# 1-Schematic__980.net
KiCad netlist of a schematic drawn in EasyEDA
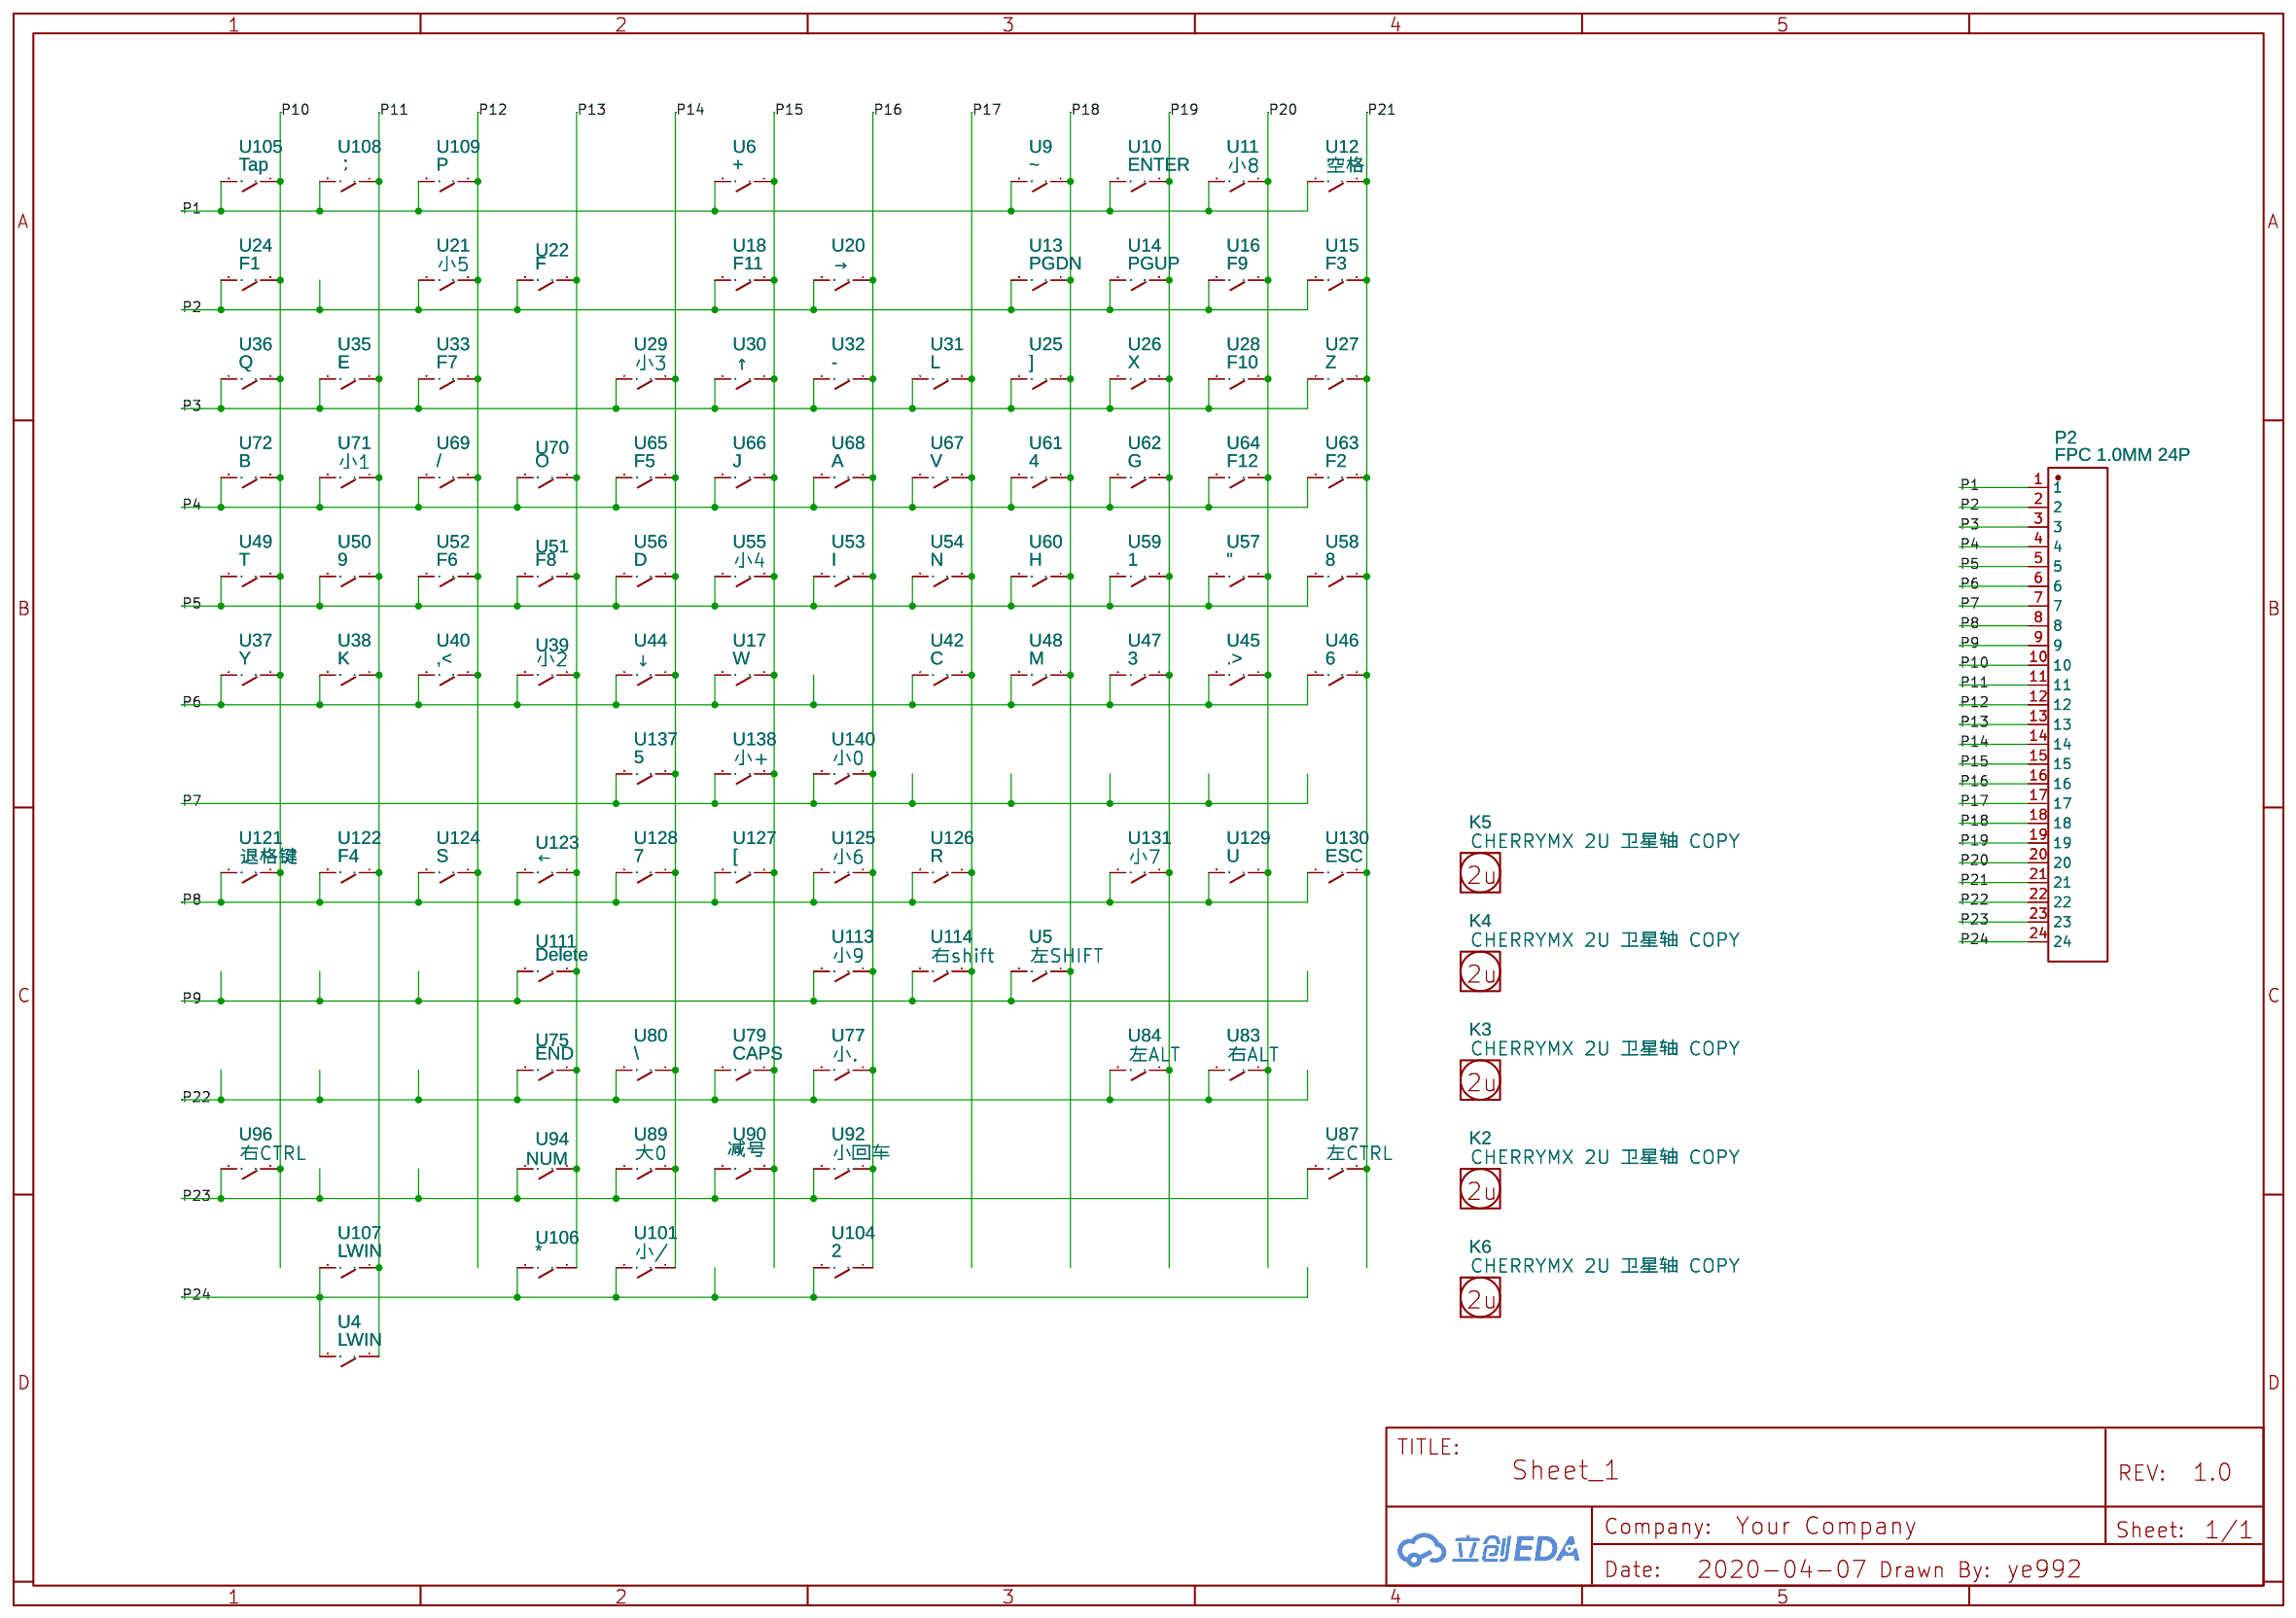
[diagram p0: 布局]
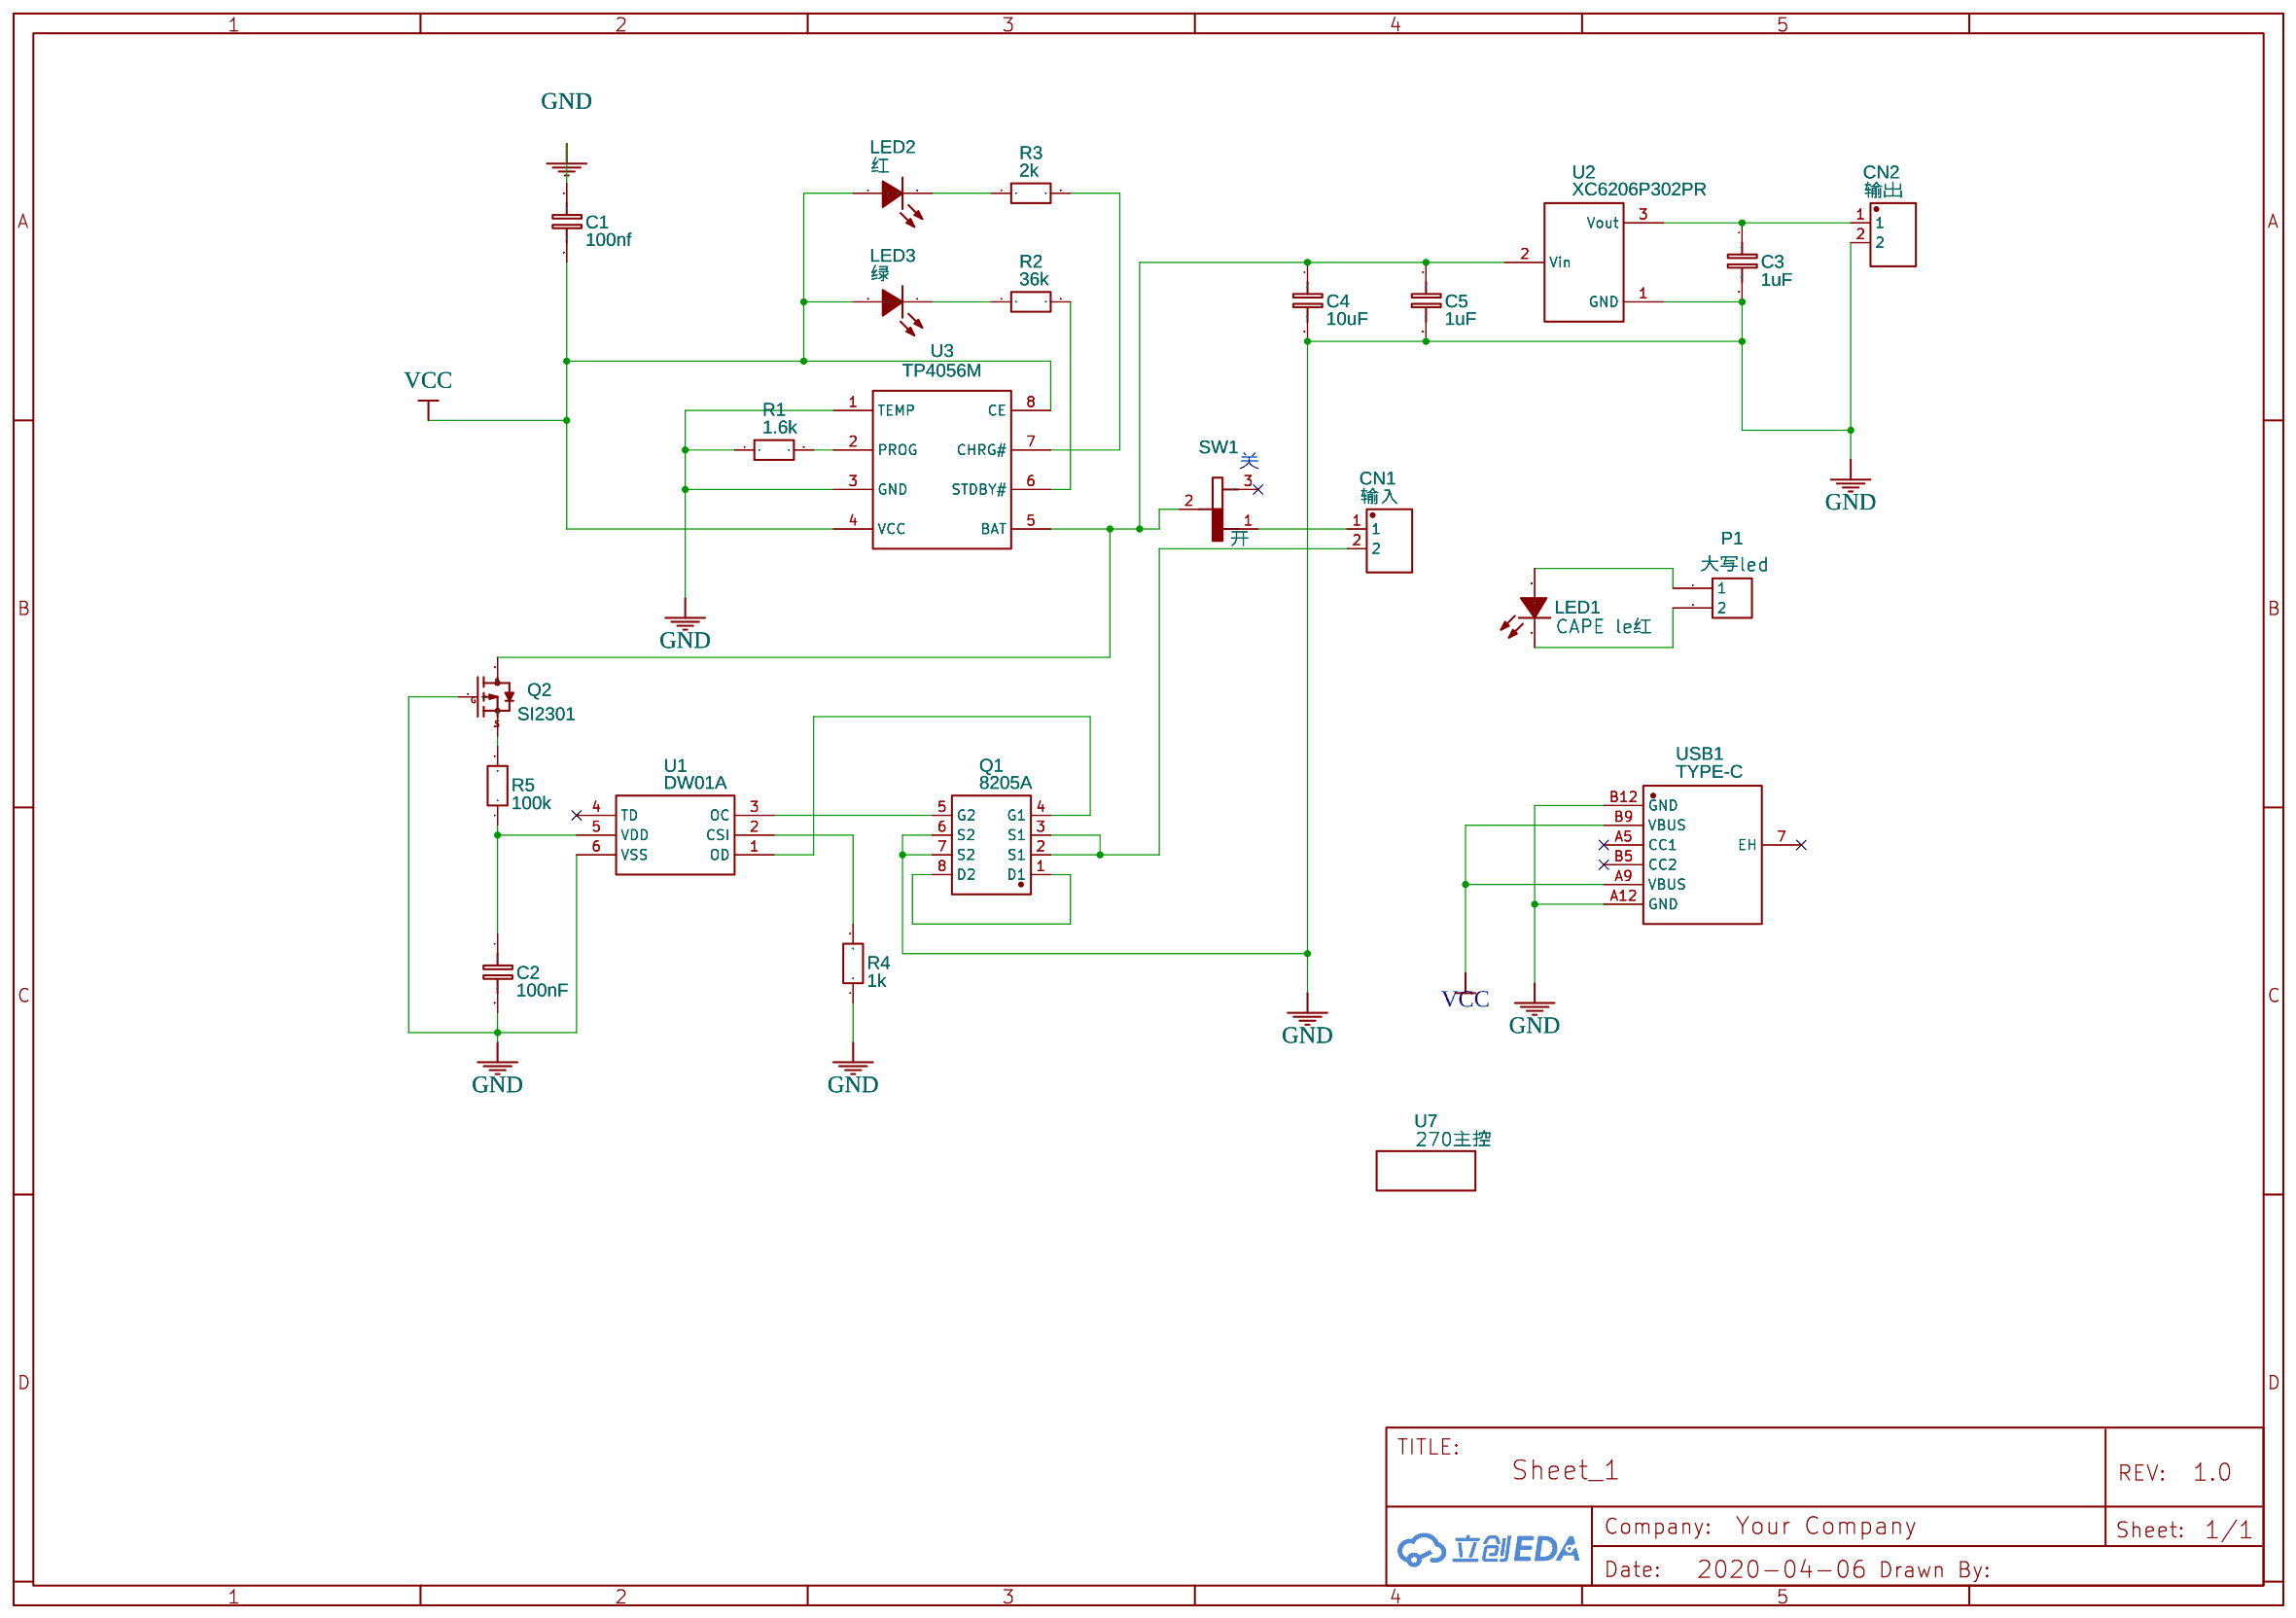
[diagram p1: Sheet_1]

(export (version "E")
  (design (tool "Eeschema 10.0.6"))
  (components
    (comp (ref "K2")
      (value "CHERRYMX 2U 卫星轴 COPY")
      (fields (field (name "BOM_Manufacturer Part") "Cherry MX"))
      (libsource (lib "") (part "CHERRYMX 2U 卫星轴 COPY"))
    )
    (comp (ref "K3")
      (value "CHERRYMX 2U 卫星轴 COPY")
      (fields (field (name "BOM_Manufacturer Part") "Cherry MX"))
      (libsource (lib "") (part "CHERRYMX 2U 卫星轴 COPY"))
    )
    (comp (ref "K4")
      (value "CHERRYMX 2U 卫星轴 COPY")
      (fields (field (name "BOM_Manufacturer Part") "Cherry MX"))
      (libsource (lib "") (part "CHERRYMX 2U 卫星轴 COPY"))
    )
    (comp (ref "K5")
      (value "CHERRYMX 2U 卫星轴 COPY")
      (fields (field (name "BOM_Manufacturer Part") "Cherry MX"))
      (libsource (lib "") (part "CHERRYMX 2U 卫星轴 COPY"))
    )
    (comp (ref "K6")
      (value "CHERRYMX 2U 卫星轴 COPY")
      (fields (field (name "BOM_Manufacturer Part") "Cherry MX"))
      (libsource (lib "") (part "CHERRYMX 2U 卫星轴 COPY"))
    )
    (comp (ref "P2")
      (value "FPC 1.0MM 24P")
      (fields
        (field (name "BOM_Manufacturer Part") "FPC 1.0mmpitch 24P Pull type Under the next")
        (field (name "BOM_Supplier Part") "C48186")
      )
      (libsource (lib "") (part "fpc24p （FPC 1.0MM 24P NO CONNECTOR）"))
    )
    (comp (ref "U4") (value "LWIN") (libsource (lib "") (part "CHERRY")))
    (comp (ref "U5") (value "左SHIFT") (libsource (lib "") (part "CHERRY")))
    (comp (ref "U6") (value "+") (libsource (lib "") (part "CHERRY")))
    (comp (ref "U9") (value "~") (libsource (lib "") (part "CHERRY")))
    (comp (ref "U10") (value "ENTER") (libsource (lib "") (part "CHERRY")))
    (comp (ref "U11") (value "小8") (libsource (lib "") (part "CHERRY")))
    (comp (ref "U12") (value "空格") (libsource (lib "") (part "CHERRY")))
    (comp (ref "U13") (value "PGDN") (libsource (lib "") (part "CHERRY")))
    (comp (ref "U14") (value "PGUP") (libsource (lib "") (part "CHERRY")))
    (comp (ref "U15") (value "F3") (libsource (lib "") (part "CHERRY")))
    (comp (ref "U16") (value "F9") (libsource (lib "") (part "CHERRY")))
    (comp (ref "U17") (value "W") (libsource (lib "") (part "CHERRY")))
    (comp (ref "U18") (value "F11") (libsource (lib "") (part "CHERRY")))
    (comp (ref "U20") (value "→") (libsource (lib "") (part "CHERRY")))
    (comp (ref "U21") (value "小5") (libsource (lib "") (part "CHERRY")))
    (comp (ref "U22") (value "F") (libsource (lib "") (part "CHERRY")))
    (comp (ref "U24") (value "F1") (libsource (lib "") (part "CHERRY")))
    (comp (ref "U25") (value "]") (libsource (lib "") (part "CHERRY")))
    (comp (ref "U26") (value "X") (libsource (lib "") (part "CHERRY")))
    (comp (ref "U27") (value "Z") (libsource (lib "") (part "CHERRY")))
    (comp (ref "U28") (value "F10") (libsource (lib "") (part "CHERRY")))
    (comp (ref "U29") (value "小3") (libsource (lib "") (part "CHERRY")))
    (comp (ref "U30") (value "↑") (libsource (lib "") (part "CHERRY")))
    (comp (ref "U31") (value "L") (libsource (lib "") (part "CHERRY")))
    (comp (ref "U32") (value "-") (libsource (lib "") (part "CHERRY")))
    (comp (ref "U33") (value "F7") (libsource (lib "") (part "CHERRY")))
    (comp (ref "U35") (value "E") (libsource (lib "") (part "CHERRY")))
    (comp (ref "U36") (value "Q") (libsource (lib "") (part "CHERRY")))
    (comp (ref "U37") (value "Y") (libsource (lib "") (part "CHERRY")))
    (comp (ref "U38") (value "K") (libsource (lib "") (part "CHERRY")))
    (comp (ref "U39") (value "小2") (libsource (lib "") (part "CHERRY")))
    (comp (ref "U40") (value ",<") (libsource (lib "") (part "CHERRY")))
    (comp (ref "U42") (value "C") (libsource (lib "") (part "CHERRY")))
    (comp (ref "U44") (value "↓") (libsource (lib "") (part "CHERRY")))
    (comp (ref "U45") (value ".>") (libsource (lib "") (part "CHERRY")))
    (comp (ref "U46") (value "6") (libsource (lib "") (part "CHERRY")))
    (comp (ref "U47") (value "3") (libsource (lib "") (part "CHERRY")))
    (comp (ref "U48") (value "M") (libsource (lib "") (part "CHERRY")))
    (comp (ref "U49") (value "T") (libsource (lib "") (part "CHERRY")))
    (comp (ref "U50") (value "9") (libsource (lib "") (part "CHERRY")))
    (comp (ref "U51") (value "F8") (libsource (lib "") (part "CHERRY")))
    (comp (ref "U52") (value "F6") (libsource (lib "") (part "CHERRY")))
    (comp (ref "U53") (value "I") (libsource (lib "") (part "CHERRY")))
    (comp (ref "U54") (value "N") (libsource (lib "") (part "CHERRY")))
    (comp (ref "U55") (value "小4") (libsource (lib "") (part "CHERRY")))
    (comp (ref "U56") (value "D") (libsource (lib "") (part "CHERRY")))
    (comp (ref "U57") (value "\"") (libsource (lib "") (part "CHERRY")))
    (comp (ref "U58") (value "8") (libsource (lib "") (part "CHERRY")))
    (comp (ref "U59") (value "1") (libsource (lib "") (part "CHERRY")))
    (comp (ref "U60") (value "H") (libsource (lib "") (part "CHERRY")))
    (comp (ref "U61") (value "4") (libsource (lib "") (part "CHERRY")))
    (comp (ref "U62") (value "G") (libsource (lib "") (part "CHERRY")))
    (comp (ref "U63") (value "F2") (libsource (lib "") (part "CHERRY")))
    (comp (ref "U64") (value "F12") (libsource (lib "") (part "CHERRY")))
    (comp (ref "U65") (value "F5") (libsource (lib "") (part "CHERRY")))
    (comp (ref "U66") (value "J") (libsource (lib "") (part "CHERRY")))
    (comp (ref "U67") (value "V") (libsource (lib "") (part "CHERRY")))
    (comp (ref "U68") (value "A") (libsource (lib "") (part "CHERRY")))
    (comp (ref "U69") (value "/") (libsource (lib "") (part "CHERRY")))
    (comp (ref "U70") (value "O") (libsource (lib "") (part "CHERRY")))
    (comp (ref "U71") (value "小1") (libsource (lib "") (part "CHERRY")))
    (comp (ref "U72") (value "B") (libsource (lib "") (part "CHERRY")))
    (comp (ref "U75") (value "END") (libsource (lib "") (part "CHERRY")))
    (comp (ref "U77") (value "小.") (libsource (lib "") (part "CHERRY")))
    (comp (ref "U79") (value "CAPS") (libsource (lib "") (part "CHERRY")))
    (comp (ref "U80") (value "\\") (libsource (lib "") (part "CHERRY")))
    (comp (ref "U83") (value "右ALT") (libsource (lib "") (part "CHERRY")))
    (comp (ref "U84") (value "左ALT") (libsource (lib "") (part "CHERRY")))
    (comp (ref "U87") (value "左CTRL") (libsource (lib "") (part "CHERRY")))
    (comp (ref "U89") (value "大0") (libsource (lib "") (part "CHERRY")))
    (comp (ref "U90") (value "减号") (libsource (lib "") (part "CHERRY")))
    (comp (ref "U92") (value "小回车") (libsource (lib "") (part "CHERRY")))
    (comp (ref "U94") (value "NUM") (libsource (lib "") (part "CHERRY")))
    (comp (ref "U96") (value "右CTRL") (libsource (lib "") (part "CHERRY")))
    (comp (ref "U101") (value "小/") (libsource (lib "") (part "CHERRY")))
    (comp (ref "U104") (value "2") (libsource (lib "") (part "CHERRY")))
    (comp (ref "U105") (value "Tap") (libsource (lib "") (part "CHERRY")))
    (comp (ref "U106") (value "*") (libsource (lib "") (part "CHERRY")))
    (comp (ref "U107") (value "LWIN") (libsource (lib "") (part "CHERRY")))
    (comp (ref "U108") (value "；") (libsource (lib "") (part "CHERRY")))
    (comp (ref "U109") (value "P") (libsource (lib "") (part "CHERRY")))
    (comp (ref "U111") (value "Delete") (libsource (lib "") (part "CHERRY")))
    (comp (ref "U113") (value "小9") (libsource (lib "") (part "CHERRY")))
    (comp (ref "U114") (value "右shift") (libsource (lib "") (part "CHERRY")))
    (comp (ref "U121") (value "退格键") (libsource (lib "") (part "CHERRY")))
    (comp (ref "U122") (value "F4") (libsource (lib "") (part "CHERRY")))
    (comp (ref "U123") (value "←") (libsource (lib "") (part "CHERRY")))
    (comp (ref "U124") (value "S") (libsource (lib "") (part "CHERRY")))
    (comp (ref "U125") (value "小6") (libsource (lib "") (part "CHERRY")))
    (comp (ref "U126") (value "R") (libsource (lib "") (part "CHERRY")))
    (comp (ref "U127") (value "[") (libsource (lib "") (part "CHERRY")))
    (comp (ref "U128") (value "7") (libsource (lib "") (part "CHERRY")))
    (comp (ref "U129") (value "U") (libsource (lib "") (part "CHERRY")))
    (comp (ref "U130") (value "ESC") (libsource (lib "") (part "CHERRY")))
    (comp (ref "U131") (value "小7") (libsource (lib "") (part "CHERRY")))
    (comp (ref "U137") (value "5") (libsource (lib "") (part "CHERRY")))
    (comp (ref "U138") (value "小+") (libsource (lib "") (part "CHERRY")))
    (comp (ref "U140") (value "小0") (libsource (lib "") (part "CHERRY")))
    (comp (ref "C1") (value "100nf") (libsource (lib "") (part "Cap_1206_EU")))
    (comp (ref "C2") (value "100nF") (libsource (lib "") (part "Cap_1206_EU_2")))
    (comp (ref "C3") (value "1uF") (libsource (lib "") (part "Cap_1206_EU_1")))
    (comp (ref "C4") (value "10uF") (libsource (lib "") (part "Cap_1206_EU_1")))
    (comp (ref "C5") (value "1uF") (libsource (lib "") (part "Cap_1206_EU_1")))
    (comp (ref "CN1")
      (value "输入")
      (fields (field (name "BOM_Manufacturer Part") "2510S-2P") (field (name "BOM_Supplier Part") "C132504"))
      (libsource (lib "") (part "2510S-2P"))
    )
    (comp (ref "CN2")
      (value "输出")
      (fields (field (name "BOM_Manufacturer Part") "2510S-2P") (field (name "BOM_Supplier Part") "C132504"))
      (libsource (lib "") (part "2510S-2P"))
    )
    (comp (ref "LED1")
      (value "CAPE le红")
      (fields
        (field (name "BOM_Manufacturer Part") "FC-3215HRK-620D")
        (field (name "BOM_Supplier Part") "C84270")
      )
      (libsource (lib "") (part "FC-3215HRK-620D"))
    )
    (comp (ref "LED2")
      (value "红")
      (fields
        (field (name "BOM_Manufacturer Part") "FC-3215HRK-620D")
        (field (name "BOM_Supplier Part") "C84270")
      )
      (libsource (lib "") (part "FC-3215HRK-620D_1"))
    )
    (comp (ref "LED3")
      (value "绿")
      (fields
        (field (name "BOM_Manufacturer Part") "FC-3215UGK-520D")
        (field (name "BOM_Supplier Part") "C99881")
      )
      (libsource (lib "") (part "FC-3215UGK-520D"))
    )
    (comp (ref "P1")
      (value "大写led")
      (fields
        (field (name "BOM_Manufacturer Part") "2.54mm 1*2P")
        (field (name "BOM_Supplier Part") "C36717")
      )
      (libsource (lib "") (part "2.54mm 1*2P"))
    )
    (comp (ref "Q1")
      (value "8205A")
      (fields (field (name "BOM_Supplier Part") "C181100"))
      (libsource (lib "") (part "8205A"))
    )
    (comp (ref "Q2")
      (value "SI2301")
      (fields (field (name "BOM_Supplier Part") "C181086"))
      (libsource (lib "") (part "SI2301"))
    )
    (comp (ref "R1") (value "1.6k") (libsource (lib "") (part "Res_1206(1/4W)_EU_1")))
    (comp (ref "R2") (value "36k") (libsource (lib "") (part "Res_1206(1/4W)_EU_1")))
    (comp (ref "R3") (value "2k") (libsource (lib "") (part "Res_1206(1/4W)_EU_1")))
    (comp (ref "R4") (value "1k") (libsource (lib "") (part "Res_1206(1/4W)_EU")))
    (comp (ref "R5") (value "100k") (libsource (lib "") (part "Res_1206(1/4W)_EU")))
    (comp (ref "SW1")
      (value "开")
      (fields
        (field (name "BOM_Manufacturer Part") "CSJ-1206-PAP31-14R")
        (field (name "BOM_Supplier Part") "C248278")
      )
      (libsource (lib "") (part "CSJ-1206-PAP31-14R"))
    )
    (comp (ref "U1")
      (value "DW01A")
      (fields (field (name "BOM_Supplier Part") "C85680"))
      (libsource (lib "") (part "DW01A"))
    )
    (comp (ref "U2")
      (value "XC6206P302PR")
      (fields (field (name "BOM_Supplier Part") "C34506"))
      (libsource (lib "") (part "XC6206P302PR"))
    )
    (comp (ref "U3")
      (value "TP4056M")
      (fields (field (name "BOM_Supplier Part") "C21417"))
      (libsource (lib "") (part "TP4056M"))
    )
    (comp (ref "U7") (value "270主控") (libsource (lib "") (part "270主控")))
    (comp (ref "USB1")
      (value "TYPE-C")
      (fields (field (name "BOM_Manufacturer Part") "TYPE-C 6P") (field (name "BOM_Supplier Part") "C456012"))
      (libsource (lib "") (part "TYPE-C 6P"))
    )
  )
  (nets
    (net (code "1") (name "GND") (class "Default")
      (node (ref "C1") (pin "1") (pinfunction "1_1") (pintype "unspecified"))
      (node (ref "C2") (pin "2") (pinfunction "2_2") (pintype "unspecified"))
      (node (ref "C3") (pin "2") (pinfunction "2_2") (pintype "unspecified"))
      (node (ref "C4") (pin "2") (pinfunction "2_2") (pintype "unspecified"))
      (node (ref "C5") (pin "2") (pinfunction "2_2") (pintype "unspecified"))
      (node (ref "CN2") (pin "2") (pinfunction "2_2") (pintype "unspecified"))
      (node (ref "Q1") (pin "6") (pinfunction "S2_6") (pintype "unspecified"))
      (node (ref "Q1") (pin "7") (pinfunction "S2_7") (pintype "unspecified"))
      (node (ref "Q2") (pin "1") (pinfunction "G_1") (pintype "unspecified"))
      (node (ref "R1") (pin "1") (pinfunction "1_1") (pintype "unspecified"))
      (node (ref "R4") (pin "1") (pinfunction "1_1") (pintype "unspecified"))
      (node (ref "U1") (pin "6") (pinfunction "VSS_6") (pintype "unspecified"))
      (node (ref "U2") (pin "1") (pinfunction "GND_1") (pintype "unspecified"))
      (node (ref "U3") (pin "1") (pinfunction "TEMP_1") (pintype "unspecified"))
      (node (ref "U3") (pin "3") (pinfunction "GND_3") (pintype "unspecified"))
      (node (ref "USB1") (pin "A12") (pinfunction "GND_A12") (pintype "unspecified"))
      (node (ref "USB1") (pin "B12") (pinfunction "GND_B12") (pintype "unspecified"))
    )
    (net (code "2") (name "Net-(CN1-Pad1)") (class "Default")
      (node (ref "CN1") (pin "1") (pinfunction "1_1") (pintype "unspecified"))
      (node (ref "SW1") (pin "1") (pinfunction "1_1") (pintype "unspecified"))
    )
    (net (code "3") (name "Net-(CN1-Pad2)") (class "Default")
      (node (ref "CN1") (pin "2") (pinfunction "2_2") (pintype "unspecified"))
      (node (ref "Q1") (pin "2") (pinfunction "S1_2") (pintype "unspecified"))
      (node (ref "Q1") (pin "3") (pinfunction "S1_3") (pintype "unspecified"))
    )
    (net (code "4") (name "Net-(LED1-A)") (class "Default")
      (node (ref "LED1") (pin "1") (pinfunction "A_1") (pintype "unspecified"))
      (node (ref "P1") (pin "1") (pinfunction "1_1") (pintype "input"))
    )
    (net (code "5") (name "Net-(LED1-K)") (class "Default")
      (node (ref "LED1") (pin "2") (pinfunction "K_2") (pintype "unspecified"))
      (node (ref "P1") (pin "2") (pinfunction "2_2") (pintype "input"))
    )
    (net (code "6") (name "Net-(LED2-K)") (class "Default")
      (node (ref "LED2") (pin "2") (pinfunction "K_2") (pintype "unspecified"))
      (node (ref "R3") (pin "1") (pinfunction "1_1") (pintype "unspecified"))
    )
    (net (code "7") (name "Net-(LED3--)") (class "Default")
      (node (ref "LED3") (pin "1") (pinfunction "-_1") (pintype "unspecified"))
      (node (ref "R2") (pin "1") (pinfunction "1_1") (pintype "unspecified"))
    )
    (net (code "8") (name "Net-(Q1-D1)") (class "Default")
      (node (ref "Q1") (pin "1") (pinfunction "D1_1") (pintype "unspecified"))
      (node (ref "Q1") (pin "8") (pinfunction "D2_8") (pintype "unspecified"))
    )
    (net (code "9") (name "Net-(Q1-G1)") (class "Default")
      (node (ref "Q1") (pin "4") (pinfunction "G1_4") (pintype "unspecified"))
      (node (ref "U1") (pin "1") (pinfunction "OD_1") (pintype "unspecified"))
    )
    (net (code "10") (name "Net-(Q1-G2)") (class "Default")
      (node (ref "Q1") (pin "5") (pinfunction "G2_5") (pintype "unspecified"))
      (node (ref "U1") (pin "3") (pinfunction "OC_3") (pintype "unspecified"))
    )
    (net (code "11") (name "Net-(Q2-D)") (class "Default")
      (node (ref "C4") (pin "1") (pinfunction "1_1") (pintype "unspecified"))
      (node (ref "C5") (pin "1") (pinfunction "1_1") (pintype "unspecified"))
      (node (ref "Q2") (pin "3") (pinfunction "D_3") (pintype "unspecified"))
      (node (ref "SW1") (pin "2") (pinfunction "2_2") (pintype "unspecified"))
      (node (ref "U2") (pin "2") (pinfunction "Vin_2") (pintype "unspecified"))
      (node (ref "U3") (pin "5") (pinfunction "BAT_5") (pintype "unspecified"))
    )
    (net (code "12") (name "Net-(Q2-S)") (class "Default")
      (node (ref "Q2") (pin "2") (pinfunction "S_2") (pintype "unspecified"))
      (node (ref "R5") (pin "2") (pinfunction "2_2") (pintype "unspecified"))
    )
    (net (code "13") (name "Net-(U1-CSI)") (class "Default")
      (node (ref "R4") (pin "2") (pinfunction "2_2") (pintype "unspecified"))
      (node (ref "U1") (pin "2") (pinfunction "CSI_2") (pintype "unspecified"))
    )
    (net (code "14") (name "Net-(U1-VDD)") (class "Default")
      (node (ref "C2") (pin "1") (pinfunction "1_1") (pintype "unspecified"))
      (node (ref "R5") (pin "1") (pinfunction "1_1") (pintype "unspecified"))
      (node (ref "U1") (pin "5") (pinfunction "VDD_5") (pintype "unspecified"))
    )
    (net (code "15") (name "Net-(U2-Vout)") (class "Default")
      (node (ref "C3") (pin "1") (pinfunction "1_1") (pintype "unspecified"))
      (node (ref "CN2") (pin "1") (pinfunction "1_1") (pintype "unspecified"))
      (node (ref "U2") (pin "3") (pinfunction "Vout_3") (pintype "unspecified"))
    )
    (net (code "16") (name "Net-(U3-CHRG#)") (class "Default")
      (node (ref "R3") (pin "2") (pinfunction "2_2") (pintype "unspecified"))
      (node (ref "U3") (pin "7") (pinfunction "CHRG#_7") (pintype "unspecified"))
    )
    (net (code "17") (name "Net-(U3-PROG)") (class "Default")
      (node (ref "R1") (pin "2") (pinfunction "2_2") (pintype "unspecified"))
      (node (ref "U3") (pin "2") (pinfunction "PROG_2") (pintype "unspecified"))
    )
    (net (code "18") (name "Net-(U3-STDBY#)") (class "Default")
      (node (ref "R2") (pin "2") (pinfunction "2_2") (pintype "unspecified"))
      (node (ref "U3") (pin "6") (pinfunction "STDBY#_6") (pintype "unspecified"))
    )
    (net (code "19") (name "P1") (class "Default")
      (node (ref "P2") (pin "1") (pinfunction "1_1") (pintype "unspecified"))
      (node (ref "U10") (pin "2") (pinfunction "2_2") (pintype "input"))
      (node (ref "U105") (pin "2") (pinfunction "2_2") (pintype "input"))
      (node (ref "U108") (pin "2") (pinfunction "2_2") (pintype "input"))
      (node (ref "U109") (pin "2") (pinfunction "2_2") (pintype "input"))
      (node (ref "U11") (pin "2") (pinfunction "2_2") (pintype "input"))
      (node (ref "U12") (pin "2") (pinfunction "2_2") (pintype "input"))
      (node (ref "U6") (pin "2") (pinfunction "2_2") (pintype "input"))
      (node (ref "U9") (pin "2") (pinfunction "2_2") (pintype "input"))
    )
    (net (code "20") (name "P2") (class "Default")
      (node (ref "P2") (pin "2") (pinfunction "2_2") (pintype "unspecified"))
      (node (ref "U13") (pin "2") (pinfunction "2_2") (pintype "input"))
      (node (ref "U14") (pin "2") (pinfunction "2_2") (pintype "input"))
      (node (ref "U15") (pin "2") (pinfunction "2_2") (pintype "input"))
      (node (ref "U16") (pin "2") (pinfunction "2_2") (pintype "input"))
      (node (ref "U18") (pin "2") (pinfunction "2_2") (pintype "input"))
      (node (ref "U20") (pin "2") (pinfunction "2_2") (pintype "input"))
      (node (ref "U21") (pin "2") (pinfunction "2_2") (pintype "input"))
      (node (ref "U22") (pin "2") (pinfunction "2_2") (pintype "input"))
      (node (ref "U24") (pin "2") (pinfunction "2_2") (pintype "input"))
    )
    (net (code "21") (name "P3") (class "Default")
      (node (ref "P2") (pin "3") (pinfunction "3_3") (pintype "unspecified"))
      (node (ref "U25") (pin "2") (pinfunction "2_2") (pintype "input"))
      (node (ref "U26") (pin "2") (pinfunction "2_2") (pintype "input"))
      (node (ref "U27") (pin "2") (pinfunction "2_2") (pintype "input"))
      (node (ref "U28") (pin "2") (pinfunction "2_2") (pintype "input"))
      (node (ref "U29") (pin "2") (pinfunction "2_2") (pintype "input"))
      (node (ref "U30") (pin "2") (pinfunction "2_2") (pintype "input"))
      (node (ref "U31") (pin "2") (pinfunction "2_2") (pintype "input"))
      (node (ref "U32") (pin "2") (pinfunction "2_2") (pintype "input"))
      (node (ref "U33") (pin "2") (pinfunction "2_2") (pintype "input"))
      (node (ref "U35") (pin "2") (pinfunction "2_2") (pintype "input"))
      (node (ref "U36") (pin "2") (pinfunction "2_2") (pintype "input"))
    )
    (net (code "22") (name "P4") (class "Default")
      (node (ref "P2") (pin "4") (pinfunction "4_4") (pintype "unspecified"))
      (node (ref "U61") (pin "2") (pinfunction "2_2") (pintype "input"))
      (node (ref "U62") (pin "2") (pinfunction "2_2") (pintype "input"))
      (node (ref "U63") (pin "2") (pinfunction "2_2") (pintype "input"))
      (node (ref "U64") (pin "2") (pinfunction "2_2") (pintype "input"))
      (node (ref "U65") (pin "2") (pinfunction "2_2") (pintype "input"))
      (node (ref "U66") (pin "2") (pinfunction "2_2") (pintype "input"))
      (node (ref "U67") (pin "2") (pinfunction "2_2") (pintype "input"))
      (node (ref "U68") (pin "2") (pinfunction "2_2") (pintype "input"))
      (node (ref "U69") (pin "2") (pinfunction "2_2") (pintype "input"))
      (node (ref "U70") (pin "2") (pinfunction "2_2") (pintype "input"))
      (node (ref "U71") (pin "2") (pinfunction "2_2") (pintype "input"))
      (node (ref "U72") (pin "2") (pinfunction "2_2") (pintype "input"))
    )
    (net (code "23") (name "P5") (class "Default")
      (node (ref "P2") (pin "5") (pinfunction "5_5") (pintype "unspecified"))
      (node (ref "U49") (pin "2") (pinfunction "2_2") (pintype "input"))
      (node (ref "U50") (pin "2") (pinfunction "2_2") (pintype "input"))
      (node (ref "U51") (pin "2") (pinfunction "2_2") (pintype "input"))
      (node (ref "U52") (pin "2") (pinfunction "2_2") (pintype "input"))
      (node (ref "U53") (pin "2") (pinfunction "2_2") (pintype "input"))
      (node (ref "U54") (pin "2") (pinfunction "2_2") (pintype "input"))
      (node (ref "U55") (pin "2") (pinfunction "2_2") (pintype "input"))
      (node (ref "U56") (pin "2") (pinfunction "2_2") (pintype "input"))
      (node (ref "U57") (pin "2") (pinfunction "2_2") (pintype "input"))
      (node (ref "U58") (pin "2") (pinfunction "2_2") (pintype "input"))
      (node (ref "U59") (pin "2") (pinfunction "2_2") (pintype "input"))
      (node (ref "U60") (pin "2") (pinfunction "2_2") (pintype "input"))
    )
    (net (code "24") (name "P6") (class "Default")
      (node (ref "P2") (pin "6") (pinfunction "6_6") (pintype "unspecified"))
      (node (ref "U17") (pin "2") (pinfunction "2_2") (pintype "input"))
      (node (ref "U37") (pin "2") (pinfunction "2_2") (pintype "input"))
      (node (ref "U38") (pin "2") (pinfunction "2_2") (pintype "input"))
      (node (ref "U39") (pin "2") (pinfunction "2_2") (pintype "input"))
      (node (ref "U40") (pin "2") (pinfunction "2_2") (pintype "input"))
      (node (ref "U42") (pin "2") (pinfunction "2_2") (pintype "input"))
      (node (ref "U44") (pin "2") (pinfunction "2_2") (pintype "input"))
      (node (ref "U45") (pin "2") (pinfunction "2_2") (pintype "input"))
      (node (ref "U46") (pin "2") (pinfunction "2_2") (pintype "input"))
      (node (ref "U47") (pin "2") (pinfunction "2_2") (pintype "input"))
      (node (ref "U48") (pin "2") (pinfunction "2_2") (pintype "input"))
    )
    (net (code "25") (name "P7") (class "Default")
      (node (ref "P2") (pin "7") (pinfunction "7_7") (pintype "unspecified"))
      (node (ref "U137") (pin "2") (pinfunction "2_2") (pintype "input"))
      (node (ref "U138") (pin "2") (pinfunction "2_2") (pintype "input"))
      (node (ref "U140") (pin "2") (pinfunction "2_2") (pintype "input"))
    )
    (net (code "26") (name "P8") (class "Default")
      (node (ref "P2") (pin "8") (pinfunction "8_8") (pintype "unspecified"))
      (node (ref "U121") (pin "2") (pinfunction "2_2") (pintype "input"))
      (node (ref "U122") (pin "2") (pinfunction "2_2") (pintype "input"))
      (node (ref "U123") (pin "2") (pinfunction "2_2") (pintype "input"))
      (node (ref "U124") (pin "2") (pinfunction "2_2") (pintype "input"))
      (node (ref "U125") (pin "2") (pinfunction "2_2") (pintype "input"))
      (node (ref "U126") (pin "2") (pinfunction "2_2") (pintype "input"))
      (node (ref "U127") (pin "2") (pinfunction "2_2") (pintype "input"))
      (node (ref "U128") (pin "2") (pinfunction "2_2") (pintype "input"))
      (node (ref "U129") (pin "2") (pinfunction "2_2") (pintype "input"))
      (node (ref "U130") (pin "2") (pinfunction "2_2") (pintype "input"))
      (node (ref "U131") (pin "2") (pinfunction "2_2") (pintype "input"))
    )
    (net (code "27") (name "P9") (class "Default")
      (node (ref "P2") (pin "9") (pinfunction "9_9") (pintype "unspecified"))
      (node (ref "U111") (pin "2") (pinfunction "2_2") (pintype "input"))
      (node (ref "U113") (pin "2") (pinfunction "2_2") (pintype "input"))
      (node (ref "U114") (pin "2") (pinfunction "2_2") (pintype "input"))
      (node (ref "U5") (pin "2") (pinfunction "2_2") (pintype "input"))
    )
    (net (code "28") (name "P10") (class "Default")
      (node (ref "P2") (pin "10") (pinfunction "10_10") (pintype "unspecified"))
      (node (ref "U105") (pin "1") (pinfunction "1_1") (pintype "input"))
      (node (ref "U121") (pin "1") (pinfunction "1_1") (pintype "input"))
      (node (ref "U24") (pin "1") (pinfunction "1_1") (pintype "input"))
      (node (ref "U36") (pin "1") (pinfunction "1_1") (pintype "input"))
      (node (ref "U37") (pin "1") (pinfunction "1_1") (pintype "input"))
      (node (ref "U49") (pin "1") (pinfunction "1_1") (pintype "input"))
      (node (ref "U72") (pin "1") (pinfunction "1_1") (pintype "input"))
      (node (ref "U96") (pin "1") (pinfunction "1_1") (pintype "input"))
    )
    (net (code "29") (name "P11") (class "Default")
      (node (ref "P2") (pin "11") (pinfunction "11_11") (pintype "unspecified"))
      (node (ref "U107") (pin "1") (pinfunction "1_1") (pintype "input"))
      (node (ref "U108") (pin "1") (pinfunction "1_1") (pintype "input"))
      (node (ref "U122") (pin "1") (pinfunction "1_1") (pintype "input"))
      (node (ref "U35") (pin "1") (pinfunction "1_1") (pintype "input"))
      (node (ref "U38") (pin "1") (pinfunction "1_1") (pintype "input"))
      (node (ref "U4") (pin "1") (pinfunction "1_1") (pintype "input"))
      (node (ref "U50") (pin "1") (pinfunction "1_1") (pintype "input"))
      (node (ref "U71") (pin "1") (pinfunction "1_1") (pintype "input"))
    )
    (net (code "30") (name "P12") (class "Default")
      (node (ref "P2") (pin "12") (pinfunction "12_12") (pintype "unspecified"))
      (node (ref "U109") (pin "1") (pinfunction "1_1") (pintype "input"))
      (node (ref "U124") (pin "1") (pinfunction "1_1") (pintype "input"))
      (node (ref "U21") (pin "1") (pinfunction "1_1") (pintype "input"))
      (node (ref "U33") (pin "1") (pinfunction "1_1") (pintype "input"))
      (node (ref "U40") (pin "1") (pinfunction "1_1") (pintype "input"))
      (node (ref "U52") (pin "1") (pinfunction "1_1") (pintype "input"))
      (node (ref "U69") (pin "1") (pinfunction "1_1") (pintype "input"))
    )
    (net (code "31") (name "P13") (class "Default")
      (node (ref "P2") (pin "13") (pinfunction "13_13") (pintype "unspecified"))
      (node (ref "U106") (pin "1") (pinfunction "1_1") (pintype "input"))
      (node (ref "U111") (pin "1") (pinfunction "1_1") (pintype "input"))
      (node (ref "U123") (pin "1") (pinfunction "1_1") (pintype "input"))
      (node (ref "U22") (pin "1") (pinfunction "1_1") (pintype "input"))
      (node (ref "U39") (pin "1") (pinfunction "1_1") (pintype "input"))
      (node (ref "U51") (pin "1") (pinfunction "1_1") (pintype "input"))
      (node (ref "U70") (pin "1") (pinfunction "1_1") (pintype "input"))
      (node (ref "U75") (pin "1") (pinfunction "1_1") (pintype "input"))
      (node (ref "U94") (pin "1") (pinfunction "1_1") (pintype "input"))
    )
    (net (code "32") (name "P14") (class "Default")
      (node (ref "P2") (pin "14") (pinfunction "14_14") (pintype "unspecified"))
      (node (ref "U101") (pin "1") (pinfunction "1_1") (pintype "input"))
      (node (ref "U128") (pin "1") (pinfunction "1_1") (pintype "input"))
      (node (ref "U137") (pin "1") (pinfunction "1_1") (pintype "input"))
      (node (ref "U29") (pin "1") (pinfunction "1_1") (pintype "input"))
      (node (ref "U44") (pin "1") (pinfunction "1_1") (pintype "input"))
      (node (ref "U56") (pin "1") (pinfunction "1_1") (pintype "input"))
      (node (ref "U65") (pin "1") (pinfunction "1_1") (pintype "input"))
      (node (ref "U80") (pin "1") (pinfunction "1_1") (pintype "input"))
      (node (ref "U89") (pin "1") (pinfunction "1_1") (pintype "input"))
    )
    (net (code "33") (name "P15") (class "Default")
      (node (ref "P2") (pin "15") (pinfunction "15_15") (pintype "unspecified"))
      (node (ref "U127") (pin "1") (pinfunction "1_1") (pintype "input"))
      (node (ref "U138") (pin "1") (pinfunction "1_1") (pintype "input"))
      (node (ref "U17") (pin "1") (pinfunction "1_1") (pintype "input"))
      (node (ref "U18") (pin "1") (pinfunction "1_1") (pintype "input"))
      (node (ref "U30") (pin "1") (pinfunction "1_1") (pintype "input"))
      (node (ref "U55") (pin "1") (pinfunction "1_1") (pintype "input"))
      (node (ref "U6") (pin "1") (pinfunction "1_1") (pintype "input"))
      (node (ref "U66") (pin "1") (pinfunction "1_1") (pintype "input"))
      (node (ref "U79") (pin "1") (pinfunction "1_1") (pintype "input"))
      (node (ref "U90") (pin "1") (pinfunction "1_1") (pintype "input"))
    )
    (net (code "34") (name "P16") (class "Default")
      (node (ref "P2") (pin "16") (pinfunction "16_16") (pintype "unspecified"))
      (node (ref "U104") (pin "1") (pinfunction "1_1") (pintype "input"))
      (node (ref "U113") (pin "1") (pinfunction "1_1") (pintype "input"))
      (node (ref "U125") (pin "1") (pinfunction "1_1") (pintype "input"))
      (node (ref "U140") (pin "1") (pinfunction "1_1") (pintype "input"))
      (node (ref "U20") (pin "1") (pinfunction "1_1") (pintype "input"))
      (node (ref "U32") (pin "1") (pinfunction "1_1") (pintype "input"))
      (node (ref "U53") (pin "1") (pinfunction "1_1") (pintype "input"))
      (node (ref "U68") (pin "1") (pinfunction "1_1") (pintype "input"))
      (node (ref "U77") (pin "1") (pinfunction "1_1") (pintype "input"))
      (node (ref "U92") (pin "1") (pinfunction "1_1") (pintype "input"))
    )
    (net (code "35") (name "P17") (class "Default")
      (node (ref "P2") (pin "17") (pinfunction "17_17") (pintype "unspecified"))
      (node (ref "U114") (pin "1") (pinfunction "1_1") (pintype "input"))
      (node (ref "U126") (pin "1") (pinfunction "1_1") (pintype "input"))
      (node (ref "U31") (pin "1") (pinfunction "1_1") (pintype "input"))
      (node (ref "U42") (pin "1") (pinfunction "1_1") (pintype "input"))
      (node (ref "U54") (pin "1") (pinfunction "1_1") (pintype "input"))
      (node (ref "U67") (pin "1") (pinfunction "1_1") (pintype "input"))
    )
    (net (code "36") (name "P18") (class "Default")
      (node (ref "P2") (pin "18") (pinfunction "18_18") (pintype "unspecified"))
      (node (ref "U13") (pin "1") (pinfunction "1_1") (pintype "input"))
      (node (ref "U25") (pin "1") (pinfunction "1_1") (pintype "input"))
      (node (ref "U48") (pin "1") (pinfunction "1_1") (pintype "input"))
      (node (ref "U5") (pin "1") (pinfunction "1_1") (pintype "input"))
      (node (ref "U60") (pin "1") (pinfunction "1_1") (pintype "input"))
      (node (ref "U61") (pin "1") (pinfunction "1_1") (pintype "input"))
      (node (ref "U9") (pin "1") (pinfunction "1_1") (pintype "input"))
    )
    (net (code "37") (name "P19") (class "Default")
      (node (ref "P2") (pin "19") (pinfunction "19_19") (pintype "unspecified"))
      (node (ref "U10") (pin "1") (pinfunction "1_1") (pintype "input"))
      (node (ref "U131") (pin "1") (pinfunction "1_1") (pintype "input"))
      (node (ref "U14") (pin "1") (pinfunction "1_1") (pintype "input"))
      (node (ref "U26") (pin "1") (pinfunction "1_1") (pintype "input"))
      (node (ref "U47") (pin "1") (pinfunction "1_1") (pintype "input"))
      (node (ref "U59") (pin "1") (pinfunction "1_1") (pintype "input"))
      (node (ref "U62") (pin "1") (pinfunction "1_1") (pintype "input"))
      (node (ref "U84") (pin "1") (pinfunction "1_1") (pintype "input"))
    )
    (net (code "38") (name "P20") (class "Default")
      (node (ref "P2") (pin "20") (pinfunction "20_20") (pintype "unspecified"))
      (node (ref "U11") (pin "1") (pinfunction "1_1") (pintype "input"))
      (node (ref "U129") (pin "1") (pinfunction "1_1") (pintype "input"))
      (node (ref "U16") (pin "1") (pinfunction "1_1") (pintype "input"))
      (node (ref "U28") (pin "1") (pinfunction "1_1") (pintype "input"))
      (node (ref "U45") (pin "1") (pinfunction "1_1") (pintype "input"))
      (node (ref "U57") (pin "1") (pinfunction "1_1") (pintype "input"))
      (node (ref "U64") (pin "1") (pinfunction "1_1") (pintype "input"))
      (node (ref "U83") (pin "1") (pinfunction "1_1") (pintype "input"))
    )
    (net (code "39") (name "P21") (class "Default")
      (node (ref "P2") (pin "21") (pinfunction "21_21") (pintype "unspecified"))
      (node (ref "U12") (pin "1") (pinfunction "1_1") (pintype "input"))
      (node (ref "U130") (pin "1") (pinfunction "1_1") (pintype "input"))
      (node (ref "U15") (pin "1") (pinfunction "1_1") (pintype "input"))
      (node (ref "U27") (pin "1") (pinfunction "1_1") (pintype "input"))
      (node (ref "U46") (pin "1") (pinfunction "1_1") (pintype "input"))
      (node (ref "U58") (pin "1") (pinfunction "1_1") (pintype "input"))
      (node (ref "U63") (pin "1") (pinfunction "1_1") (pintype "input"))
      (node (ref "U87") (pin "1") (pinfunction "1_1") (pintype "input"))
    )
    (net (code "40") (name "P22") (class "Default")
      (node (ref "P2") (pin "22") (pinfunction "22_22") (pintype "unspecified"))
      (node (ref "U75") (pin "2") (pinfunction "2_2") (pintype "input"))
      (node (ref "U77") (pin "2") (pinfunction "2_2") (pintype "input"))
      (node (ref "U79") (pin "2") (pinfunction "2_2") (pintype "input"))
      (node (ref "U80") (pin "2") (pinfunction "2_2") (pintype "input"))
      (node (ref "U83") (pin "2") (pinfunction "2_2") (pintype "input"))
      (node (ref "U84") (pin "2") (pinfunction "2_2") (pintype "input"))
    )
    (net (code "41") (name "P23") (class "Default")
      (node (ref "P2") (pin "23") (pinfunction "23_23") (pintype "unspecified"))
      (node (ref "U87") (pin "2") (pinfunction "2_2") (pintype "input"))
      (node (ref "U89") (pin "2") (pinfunction "2_2") (pintype "input"))
      (node (ref "U90") (pin "2") (pinfunction "2_2") (pintype "input"))
      (node (ref "U92") (pin "2") (pinfunction "2_2") (pintype "input"))
      (node (ref "U94") (pin "2") (pinfunction "2_2") (pintype "input"))
      (node (ref "U96") (pin "2") (pinfunction "2_2") (pintype "input"))
    )
    (net (code "42") (name "P24") (class "Default")
      (node (ref "P2") (pin "24") (pinfunction "24_24") (pintype "unspecified"))
      (node (ref "U101") (pin "2") (pinfunction "2_2") (pintype "input"))
      (node (ref "U104") (pin "2") (pinfunction "2_2") (pintype "input"))
      (node (ref "U106") (pin "2") (pinfunction "2_2") (pintype "input"))
      (node (ref "U107") (pin "2") (pinfunction "2_2") (pintype "input"))
      (node (ref "U4") (pin "2") (pinfunction "2_2") (pintype "input"))
    )
    (net (code "43") (name "VCC") (class "Default")
      (node (ref "C1") (pin "2") (pinfunction "2_2") (pintype "unspecified"))
      (node (ref "LED2") (pin "1") (pinfunction "A_1") (pintype "unspecified"))
      (node (ref "LED3") (pin "2") (pinfunction "+_2") (pintype "unspecified"))
      (node (ref "U3") (pin "4") (pinfunction "VCC_4") (pintype "unspecified"))
      (node (ref "U3") (pin "8") (pinfunction "CE_8") (pintype "unspecified"))
      (node (ref "USB1") (pin "A9") (pinfunction "VBUS_A9") (pintype "unspecified"))
      (node (ref "USB1") (pin "B9") (pinfunction "VBUS_B9") (pintype "unspecified"))
    )
    (net (code "44") (name "unconnected-(SW1-Pad3)") (class "Default")
      (node (ref "SW1") (pin "3") (pinfunction "3_3") (pintype "unspecified+no_connect"))
    )
    (net (code "45") (name "unconnected-(U1-TD-Pad4)") (class "Default")
      (node (ref "U1") (pin "4") (pinfunction "TD_4") (pintype "unspecified+no_connect"))
    )
    (net (code "46") (name "unconnected-(USB1-CC1-PadA5)") (class "Default")
      (node (ref "USB1") (pin "A5") (pinfunction "CC1_A5") (pintype "unspecified+no_connect"))
    )
    (net (code "47") (name "unconnected-(USB1-CC2-PadB5)") (class "Default")
      (node (ref "USB1") (pin "B5") (pinfunction "CC2_B5") (pintype "unspecified+no_connect"))
    )
    (net (code "48") (name "unconnected-(USB1-EH-Pad7)") (class "Default")
      (node (ref "USB1") (pin "7") (pinfunction "EH_7") (pintype "unspecified+no_connect"))
    )
  )
)
